# BiSheA.net
KiCad netlist of a schematic drawn in Altium Designer
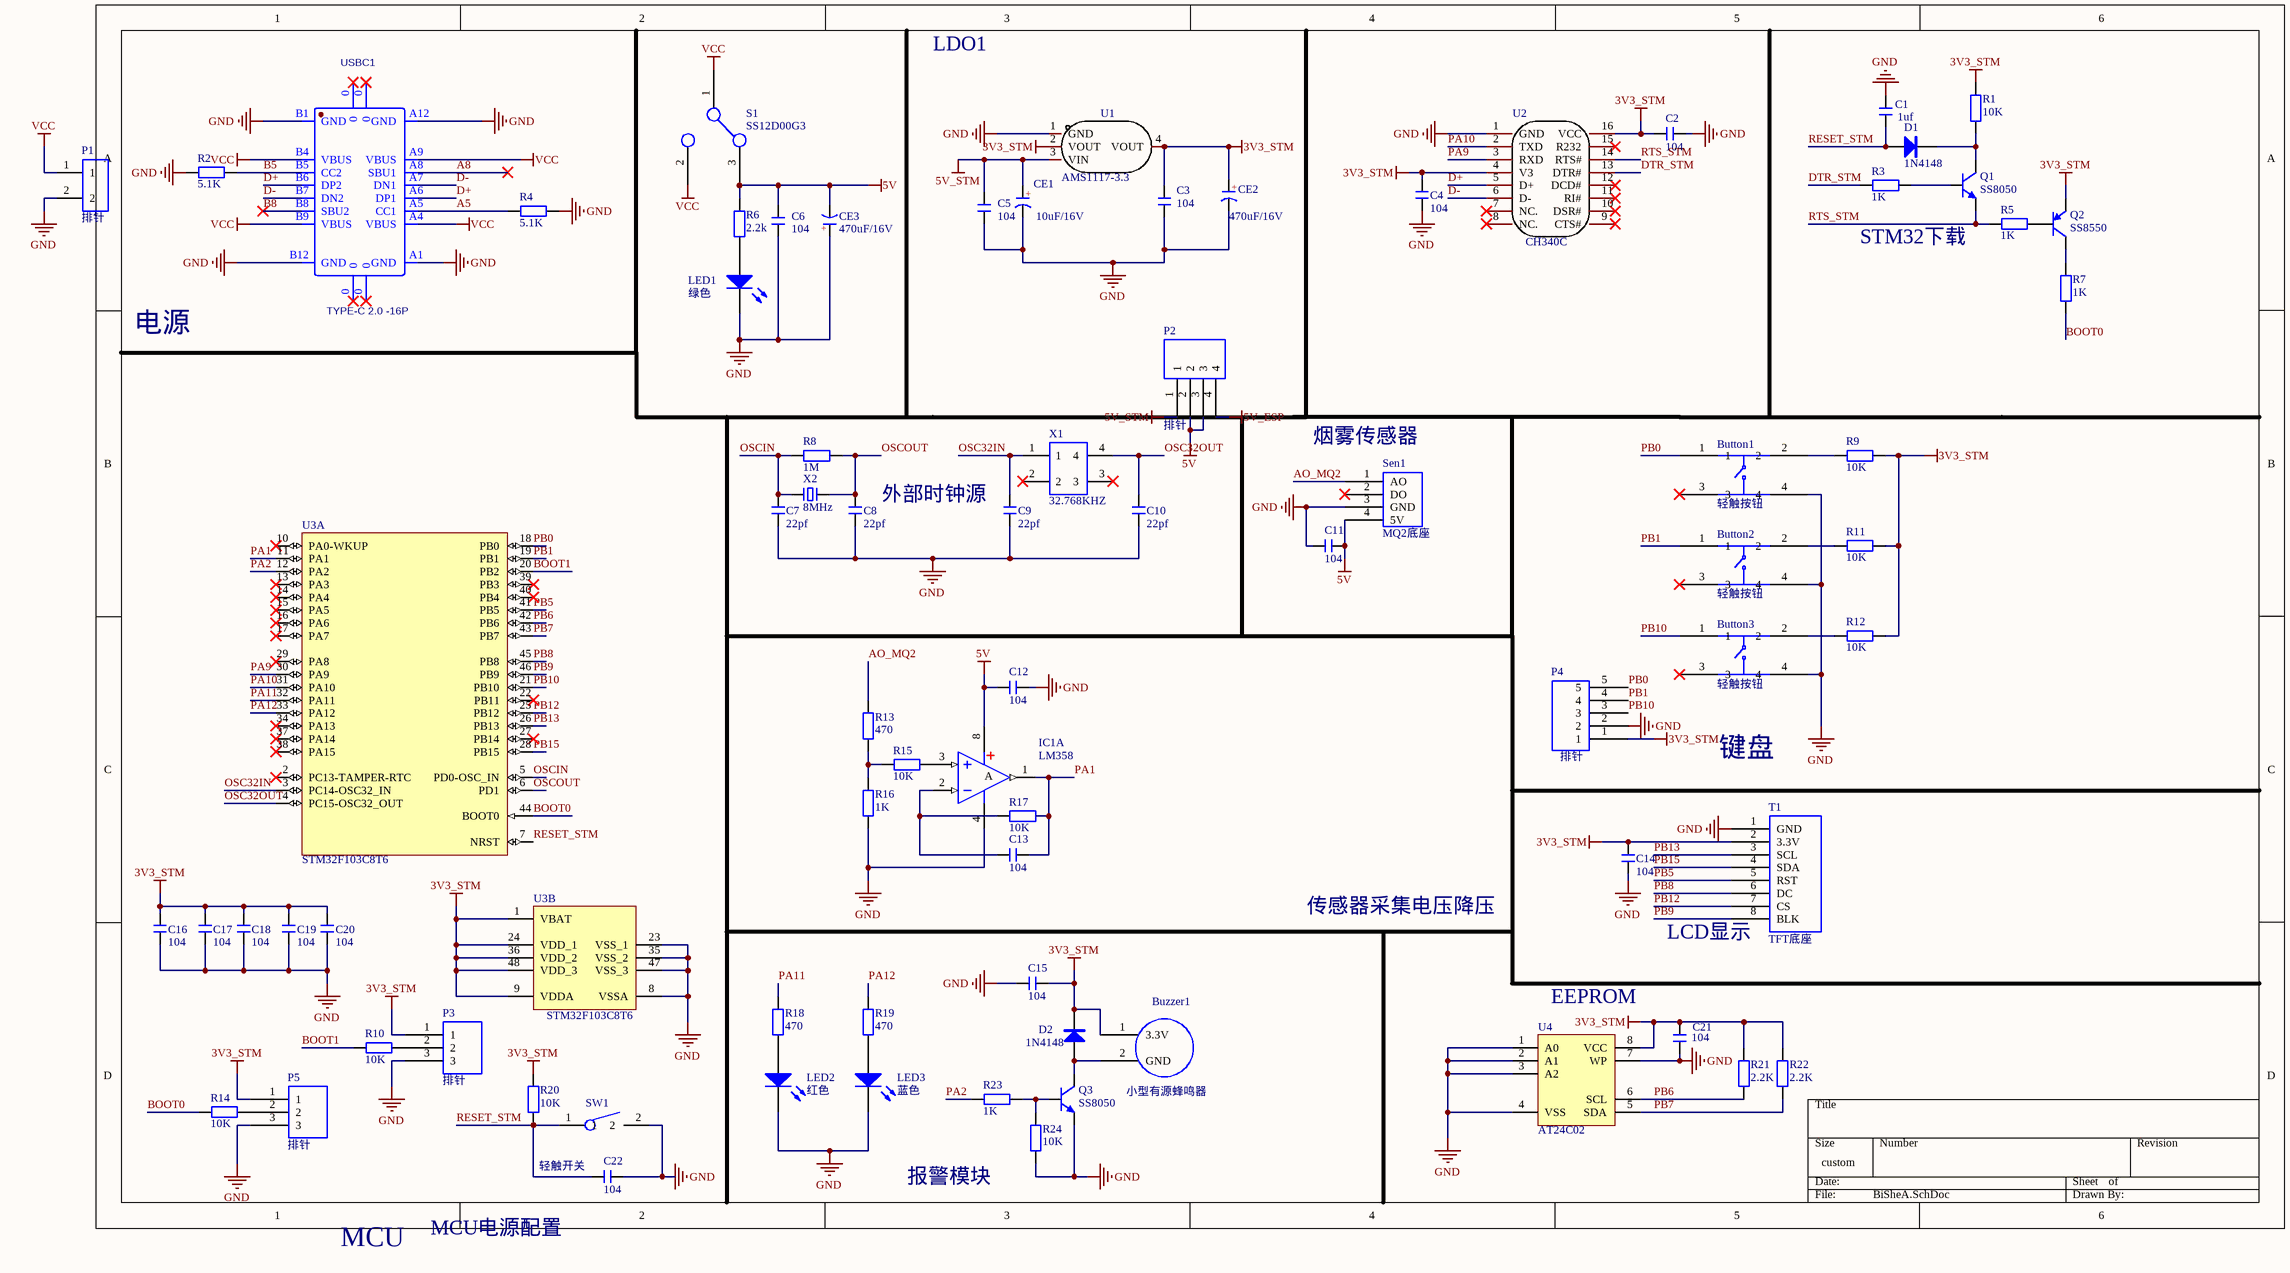
[diagram p0: BiSheA.SchDoc]

(export (version "E")
  (design (tool "Eeschema 10.0.6"))
  (components
    (comp (ref "Button1")
      (value "轻触按钮")
      (footprint "Button")
      (description "6*6*7轻触按钮")
      (libsource (lib "BiShe") (part "Button"))
    )
    (comp (ref "Button2")
      (value "轻触按钮")
      (footprint "Button")
      (description "6*6*7轻触按钮")
      (libsource (lib "BiShe") (part "Button"))
    )
    (comp (ref "Button3")
      (value "轻触按钮")
      (footprint "Button")
      (description "6*6*7轻触按钮")
      (libsource (lib "BiShe") (part "Button"))
    )
    (comp (ref "Buzzer1")
      (value "小型有源蜂鸣器")
      (footprint "Buzzer_Mini")
      (description "蜂鸣器")
      (libsource (lib "BiSheFinal") (part "Buzzer"))
    )
    (comp (ref "C1")
      (value "1uf")
      (footprint "C 0805_L")
      (description "贴片电容")
      (libsource (lib "0.1 - 电阻-电容-电感") (part "C"))
    )
    (comp (ref "C2")
      (value "104")
      (footprint "C 0805_L")
      (description "贴片电容")
      (libsource (lib "0.1 - 电阻-电容-电感") (part "C"))
    )
    (comp (ref "C3")
      (value "104")
      (footprint "C 0805_L")
      (description "贴片电容")
      (libsource (lib "0.1 - 电阻-电容-电感") (part "C"))
    )
    (comp (ref "C4")
      (value "104")
      (footprint "C 0805_L")
      (description "贴片电容")
      (libsource (lib "0.1 - 电阻-电容-电感") (part "C"))
    )
    (comp (ref "C5")
      (value "104")
      (footprint "C 0805_L")
      (description "贴片电容")
      (libsource (lib "0.1 - 电阻-电容-电感") (part "C"))
    )
    (comp (ref "C6")
      (value "104")
      (footprint "C 0805_L")
      (description "贴片电容")
      (libsource (lib "0.1 - 电阻-电容-电感") (part "C"))
    )
    (comp (ref "C7")
      (value "22pf")
      (footprint "C 0805_L")
      (description "贴片电容")
      (libsource (lib "0.1 - 电阻-电容-电感") (part "C"))
    )
    (comp (ref "C8")
      (value "22pf")
      (footprint "C 0805_L")
      (description "贴片电容")
      (libsource (lib "0.1 - 电阻-电容-电感") (part "C"))
    )
    (comp (ref "C9")
      (value "22pf")
      (footprint "C 0805_L")
      (description "贴片电容")
      (libsource (lib "0.1 - 电阻-电容-电感") (part "C"))
    )
    (comp (ref "C10")
      (value "22pf")
      (footprint "C 0805_L")
      (description "贴片电容")
      (libsource (lib "0.1 - 电阻-电容-电感") (part "C"))
    )
    (comp (ref "C11")
      (value "104")
      (footprint "C 0805_L")
      (description "贴片电容")
      (libsource (lib "0.1 - 电阻-电容-电感") (part "C"))
    )
    (comp (ref "C12")
      (value "104")
      (footprint "C 0805_L")
      (description "贴片电容")
      (libsource (lib "0.1 - 电阻-电容-电感") (part "C"))
    )
    (comp (ref "C13")
      (value "104")
      (footprint "C 0805_L")
      (description "贴片电容")
      (libsource (lib "0.1 - 电阻-电容-电感") (part "C"))
    )
    (comp (ref "C14")
      (value "104")
      (footprint "C 0805_L")
      (description "贴片电容")
      (libsource (lib "0.1 - 电阻-电容-电感") (part "C"))
    )
    (comp (ref "C15")
      (value "104")
      (footprint "C 0805_L")
      (description "贴片电容")
      (libsource (lib "0.1 - 电阻-电容-电感") (part "C"))
    )
    (comp (ref "C16")
      (value "104")
      (footprint "C 0805_L")
      (description "贴片电容")
      (libsource (lib "0.1 - 电阻-电容-电感") (part "C"))
    )
    (comp (ref "C17")
      (value "104")
      (footprint "C 0805_L")
      (description "贴片电容")
      (libsource (lib "0.1 - 电阻-电容-电感") (part "C"))
    )
    (comp (ref "C18")
      (value "104")
      (footprint "C 0805_L")
      (description "贴片电容")
      (libsource (lib "0.1 - 电阻-电容-电感") (part "C"))
    )
    (comp (ref "C19")
      (value "104")
      (footprint "C 0805_L")
      (description "贴片电容")
      (libsource (lib "0.1 - 电阻-电容-电感") (part "C"))
    )
    (comp (ref "C20")
      (value "104")
      (footprint "C 0805_L")
      (description "贴片电容")
      (libsource (lib "0.1 - 电阻-电容-电感") (part "C"))
    )
    (comp (ref "C21")
      (value "104")
      (footprint "C 0805_L")
      (description "贴片电容")
      (libsource (lib "0.1 - 电阻-电容-电感") (part "C"))
    )
    (comp (ref "C22")
      (value "104")
      (footprint "C 0805_L")
      (description "贴片电容")
      (libsource (lib "0.1 - 电阻-电容-电感") (part "C"))
    )
    (comp (ref "CE1")
      (value "10uF/16V")
      (footprint "CAP 1.5*4*8")
      (description "直插电解电容")
      (libsource (lib "0.1 - 电阻-电容-电感") (part "CE"))
    )
    (comp (ref "CE2")
      (value "470uF/16V")
      (footprint "CAP 3.5*8*11.5")
      (description "直插电解电容")
      (libsource (lib "0.1 - 电阻-电容-电感") (part "CE"))
    )
    (comp (ref "CE3")
      (value "470uF/16V")
      (footprint "CAP 3.5*8*11.5")
      (description "直插电解电容")
      (libsource (lib "0.1 - 电阻-电容-电感") (part "CE"))
    )
    (comp (ref "D1")
      (value "1N4148")
      (footprint "SOD-123")
      (description "开关二极管")
      (libsource (lib "0.2 - 二极管-整流桥") (part "1N4148"))
    )
    (comp (ref "D2")
      (value "1N4148")
      (footprint "SOD-123")
      (description "开关二极管")
      (libsource (lib "0.2 - 二极管-整流桥") (part "1N4148"))
    )
    (comp (ref "IC1")
      (value "LM358")
      (footprint "SOP8_N")
      (description "双路运放")
      (libsource (lib "1.0 - 常见芯片") (part "LM358"))
    )
    (comp (ref "LED1")
      (value "绿色")
      (footprint "LED 5MM-B")
      (description "直插5mm LED")
      (fields (field (name "版权归属") "封装库来自淘宝 ID：黄晶宝石"))
      (libsource (lib "0.3 - LED发光二极管") (part "LED-5MM"))
    )
    (comp (ref "LED2")
      (value "红色")
      (footprint "LED 5MM-B")
      (description "直插5mm LED")
      (fields (field (name "版权归属") "封装库来自淘宝 ID：黄晶宝石"))
      (libsource (lib "0.3 - LED发光二极管") (part "LED-5MM"))
    )
    (comp (ref "LED3")
      (value "蓝色")
      (footprint "LED 5MM-B")
      (description "直插5mm LED")
      (fields (field (name "版权归属") "封装库来自淘宝 ID：黄晶宝石"))
      (libsource (lib "0.3 - LED发光二极管") (part "LED-5MM"))
    )
    (comp (ref "P1")
      (value "排针")
      (footprint "2PIN")
      (description "2Pin排针")
      (libsource (lib "BiSheFinal") (part "2Pin"))
    )
    (comp (ref "P2")
      (value "排针")
      (footprint "4PIN")
      (description "4p排针")
      (libsource (lib "BiSheFinal") (part "4Pin"))
    )
    (comp (ref "P3")
      (value "排针")
      (footprint "3Pin")
      (description "3p排针")
      (libsource (lib "BiSheFinal") (part "3Pin"))
    )
    (comp (ref "P4")
      (value "排针")
      (footprint "5pin")
      (description "5Pin排针")
      (libsource (lib "BiSheFinal") (part "5Pin"))
    )
    (comp (ref "P5")
      (value "排针")
      (footprint "3Pin")
      (description "3p排针")
      (libsource (lib "BiSheFinal") (part "3Pin"))
    )
    (comp (ref "Q1")
      (value "SS8050")
      (footprint "SOT23-3N")
      (description "高频放大-NPN型")
      (fields (field (name "版权归属") "封装库来自淘宝 ID：黄晶宝石"))
      (libsource (lib "0.4 - 三极管") (part "8050-SMD"))
    )
    (comp (ref "Q2")
      (value "SS8550")
      (footprint "SOT23-3N")
      (description "高频放大-PNP型")
      (fields (field (name "版权归属") "封装库来自淘宝 ID：黄晶宝石"))
      (libsource (lib "0.4 - 三极管") (part "8550-SMD"))
    )
    (comp (ref "Q3")
      (value "SS8050")
      (footprint "SOT23-3N")
      (description "高频放大-NPN型")
      (fields (field (name "版权归属") "封装库来自淘宝 ID：黄晶宝石"))
      (libsource (lib "0.4 - 三极管") (part "8050-SMD"))
    )
    (comp (ref "R1")
      (value "10K")
      (footprint "R 0805_L")
      (description "贴片电阻")
      (fields (field (name "版权归属") "来自淘宝 ID：黄晶宝石"))
      (libsource (lib "0.1 - 电阻-电容-电感") (part "R"))
    )
    (comp (ref "R2")
      (value "5.1K")
      (footprint "R 0805_L")
      (description "贴片电阻")
      (fields (field (name "版权归属") "来自淘宝 ID：黄晶宝石"))
      (libsource (lib "0.1 - 电阻-电容-电感") (part "R"))
    )
    (comp (ref "R3")
      (value "1K")
      (footprint "R 0805_L")
      (description "贴片电阻")
      (fields (field (name "版权归属") "来自淘宝 ID：黄晶宝石"))
      (libsource (lib "0.1 - 电阻-电容-电感") (part "R"))
    )
    (comp (ref "R4")
      (value "5.1K")
      (footprint "R 0805_L")
      (description "贴片电阻")
      (fields (field (name "版权归属") "来自淘宝 ID：黄晶宝石"))
      (libsource (lib "0.1 - 电阻-电容-电感") (part "R"))
    )
    (comp (ref "R5")
      (value "1K")
      (footprint "R 0805_L")
      (description "贴片电阻")
      (fields (field (name "版权归属") "来自淘宝 ID：黄晶宝石"))
      (libsource (lib "0.1 - 电阻-电容-电感") (part "R"))
    )
    (comp (ref "R6")
      (value "2.2k")
      (footprint "R 0805_L")
      (description "贴片电阻")
      (fields (field (name "版权归属") "来自淘宝 ID：黄晶宝石"))
      (libsource (lib "0.1 - 电阻-电容-电感") (part "R"))
    )
    (comp (ref "R7")
      (value "1K")
      (footprint "R 0805_L")
      (description "贴片电阻")
      (fields (field (name "版权归属") "来自淘宝 ID：黄晶宝石"))
      (libsource (lib "0.1 - 电阻-电容-电感") (part "R"))
    )
    (comp (ref "R8")
      (value "1M")
      (footprint "R 0805_L")
      (description "贴片电阻")
      (fields (field (name "版权归属") "来自淘宝 ID：黄晶宝石"))
      (libsource (lib "0.1 - 电阻-电容-电感") (part "R"))
    )
    (comp (ref "R9")
      (value "10K")
      (footprint "R 0805_L")
      (description "贴片电阻")
      (fields (field (name "版权归属") "来自淘宝 ID：黄晶宝石"))
      (libsource (lib "0.1 - 电阻-电容-电感") (part "R"))
    )
    (comp (ref "R10")
      (value "10K")
      (footprint "R 0805_L")
      (description "贴片电阻")
      (fields (field (name "版权归属") "来自淘宝 ID：黄晶宝石"))
      (libsource (lib "0.1 - 电阻-电容-电感") (part "R"))
    )
    (comp (ref "R11")
      (value "10K")
      (footprint "R 0805_L")
      (description "贴片电阻")
      (fields (field (name "版权归属") "来自淘宝 ID：黄晶宝石"))
      (libsource (lib "0.1 - 电阻-电容-电感") (part "R"))
    )
    (comp (ref "R12")
      (value "10K")
      (footprint "R 0805_L")
      (description "贴片电阻")
      (fields (field (name "版权归属") "来自淘宝 ID：黄晶宝石"))
      (libsource (lib "0.1 - 电阻-电容-电感") (part "R"))
    )
    (comp (ref "R13")
      (value "470")
      (footprint "R 0805_L")
      (description "贴片电阻")
      (fields (field (name "版权归属") "来自淘宝 ID：黄晶宝石"))
      (libsource (lib "0.1 - 电阻-电容-电感") (part "R"))
    )
    (comp (ref "R14")
      (value "10K")
      (footprint "R 0805_L")
      (description "贴片电阻")
      (fields (field (name "版权归属") "来自淘宝 ID：黄晶宝石"))
      (libsource (lib "0.1 - 电阻-电容-电感") (part "R"))
    )
    (comp (ref "R15")
      (value "10K")
      (footprint "R 0805_L")
      (description "贴片电阻")
      (fields (field (name "版权归属") "来自淘宝 ID：黄晶宝石"))
      (libsource (lib "0.1 - 电阻-电容-电感") (part "R"))
    )
    (comp (ref "R16")
      (value "1K")
      (footprint "R 0805_L")
      (description "贴片电阻")
      (fields (field (name "版权归属") "来自淘宝 ID：黄晶宝石"))
      (libsource (lib "0.1 - 电阻-电容-电感") (part "R"))
    )
    (comp (ref "R17")
      (value "10K")
      (footprint "R 0805_L")
      (description "贴片电阻")
      (fields (field (name "版权归属") "来自淘宝 ID：黄晶宝石"))
      (libsource (lib "0.1 - 电阻-电容-电感") (part "R"))
    )
    (comp (ref "R18")
      (value "470")
      (footprint "R 0805_L")
      (description "贴片电阻")
      (fields (field (name "版权归属") "来自淘宝 ID：黄晶宝石"))
      (libsource (lib "0.1 - 电阻-电容-电感") (part "R"))
    )
    (comp (ref "R19")
      (value "470")
      (footprint "R 0805_L")
      (description "贴片电阻")
      (fields (field (name "版权归属") "来自淘宝 ID：黄晶宝石"))
      (libsource (lib "0.1 - 电阻-电容-电感") (part "R"))
    )
    (comp (ref "R20")
      (value "10K")
      (footprint "R 0805_L")
      (description "贴片电阻")
      (fields (field (name "版权归属") "来自淘宝 ID：黄晶宝石"))
      (libsource (lib "0.1 - 电阻-电容-电感") (part "R"))
    )
    (comp (ref "R21")
      (value "2.2K")
      (footprint "R 0805_L")
      (description "贴片电阻")
      (fields (field (name "版权归属") "来自淘宝 ID：黄晶宝石"))
      (libsource (lib "0.1 - 电阻-电容-电感") (part "R"))
    )
    (comp (ref "R22")
      (value "2.2K")
      (footprint "R 0805_L")
      (description "贴片电阻")
      (fields (field (name "版权归属") "来自淘宝 ID：黄晶宝石"))
      (libsource (lib "0.1 - 电阻-电容-电感") (part "R"))
    )
    (comp (ref "R23")
      (value "1K")
      (footprint "R 0805_L")
      (description "贴片电阻")
      (fields (field (name "版权归属") "来自淘宝 ID：黄晶宝石"))
      (libsource (lib "0.1 - 电阻-电容-电感") (part "R"))
    )
    (comp (ref "R24")
      (value "10K")
      (footprint "R 0805_L")
      (description "贴片电阻")
      (fields (field (name "版权归属") "来自淘宝 ID：黄晶宝石"))
      (libsource (lib "0.1 - 电阻-电容-电感") (part "R"))
    )
    (comp (ref "S1")
      (value "SS12D00G3")
      (footprint "SS12D00G3")
      (description "拨动开关")
      (libsource (lib "BiSheFinal") (part "SS12D00G3"))
    )
    (comp (ref "Sen1")
      (value "MQ2底座")
      (footprint "MQ2底座")
      (description "气体传感器")
      (libsource (lib "BiSheFinal") (part "MQ2底座"))
    )
    (comp (ref "SW1")
      (value "轻触开关")
      (footprint "SW1P")
      (description "单刀单掷清除开关")
      (libsource (lib "BiSheFinal") (part "SW1P"))
    )
    (comp (ref "T1")
      (value "TFT底座")
      (footprint "TFT底座")
      (description "底座")
      (libsource (lib "BiSheFinal") (part "TFT底座"))
    )
    (comp (ref "U1")
      (value "AMS1117-3.3")
      (footprint "SOT-223-3_L6.5-W3.4-P2.30-LS7.0-BR")
      (description "输出类型:固定;输出极性:正;最大输入电压:-;输出电压:3.3V;输出电流:1A;电源纹波抑制比(PSRR):72dB@(120Hz);")
      (fields (field (name "MANUFACTURER") "AMS") (field (name "AMS1117") "AMS1117-3.3"))
      (libsource (lib "BiSheFinal") (part "AMS1117-3.3_C6186"))
    )
    (comp (ref "U2")
      (value "CH340C")
      (footprint "SOP-16_L10.0-W3.9-P1.27-LS6.0-BL")
      (description "驱动器/接收器数:-;协议类别:USB 2.0;类型:Transceiver;数据速率:2Mbps;")
      (fields (field (name "MANUFACTURER") "WCH(南京沁恒)") (field (name "CH340C") "CH340C"))
      (libsource (lib "BiSheFinal") (part "CH340C"))
    )
    (comp (ref "U3")
      (value "STM32F103C8T6")
      (footprint "LQFP48_N")
      (libsource (lib "2.3 - STM32 F1系列单片机") (part "STM32F103C8T6"))
    )
    (comp (ref "U4")
      (value "AT24C02")
      (footprint "SOIC8_N")
      (description "EEROM存储器")
      (libsource (lib "1.0 - 常见芯片") (part "AT24C02"))
    )
    (comp (ref "USBC1")
      (value "TYPE-C 2.0 -16P")
      (footprint "USB-C-SMD_TYPE-C-USB-5")
      (description "USB2.0 Type-C 母座 16Pin")
      (libsource (lib "BiSheFinal") (part "USB2.0 Type-C 16Pin母座"))
    )
    (comp (ref "X1")
      (value "32.768KHZ")
      (footprint "MC-306")
      (description "贴片32.768KHZ")
      (libsource (lib "BiSheFinal") (part "MC-306"))
    )
    (comp (ref "X2")
      (value "8MHz")
      (footprint "OSC HC-49S")
      (description "2脚无源脚晶振")
      (fields (field (name "版权归属") "封装库来自淘宝卖家 ID：黄晶宝石"))
      (libsource (lib "2.0 - 保险丝-晶振-光耦") (part "XTAL-2P"))
    )
  )
  (nets
    (net (code "1") (name "/A5") (class "Default")
      (node (ref "R4") (pin "2") (pinfunction "2_2") (pintype "passive"))
      (node (ref "USBC1") (pin "A5") (pinfunction "CC1_A5") (pintype "passive"))
    )
    (net (code "2") (name "/A8") (class "Default")
      (node (ref "USBC1") (pin "A8") (pinfunction "SBU1_A8") (pintype "passive+no_connect"))
    )
    (net (code "3") (name "/AO_MQ2") (class "Default")
      (node (ref "R13") (pin "1") (pinfunction "1_1") (pintype "passive"))
      (node (ref "Sen1") (pin "1") (pinfunction "AO_1") (pintype "passive"))
    )
    (net (code "4") (name "/B5") (class "Default")
      (node (ref "R2") (pin "1") (pinfunction "1_1") (pintype "passive"))
      (node (ref "USBC1") (pin "B5") (pinfunction "CC2_B5") (pintype "passive"))
    )
    (net (code "5") (name "/B8") (class "Default")
      (node (ref "USBC1") (pin "B8") (pinfunction "SBU2_B8") (pintype "passive+no_connect"))
    )
    (net (code "6") (name "/BOOT0") (class "Default")
      (node (ref "R14") (pin "2") (pinfunction "2_2") (pintype "passive"))
      (node (ref "R7") (pin "2") (pinfunction "2_2") (pintype "passive"))
      (node (ref "U3") (pin "44") (pinfunction "BOOT0_44") (pintype "input"))
    )
    (net (code "7") (name "/BOOT1") (class "Default")
      (node (ref "R10") (pin "2") (pinfunction "2_2") (pintype "passive"))
      (node (ref "U3") (pin "20") (pinfunction "PB2_20") (pintype "bidirectional"))
    )
    (net (code "8") (name "/D+") (class "Default")
      (node (ref "U2") (pin "5") (pinfunction "D+_5") (pintype "passive"))
      (node (ref "USBC1") (pin "A6") (pinfunction "DP1_A6") (pintype "passive"))
      (node (ref "USBC1") (pin "B6") (pinfunction "DP2_B6") (pintype "passive"))
    )
    (net (code "9") (name "/D-") (class "Default")
      (node (ref "U2") (pin "6") (pinfunction "D-_6") (pintype "passive"))
      (node (ref "USBC1") (pin "A7") (pinfunction "DN1_A7") (pintype "passive"))
      (node (ref "USBC1") (pin "B7") (pinfunction "DN2_B7") (pintype "passive"))
    )
    (net (code "10") (name "/DTR_STM") (class "Default")
      (node (ref "R3") (pin "1") (pinfunction "1_1") (pintype "passive"))
      (node (ref "U2") (pin "13") (pinfunction "DTR#_13") (pintype "passive"))
    )
    (net (code "11") (name "/OSC32IN") (class "Default")
      (node (ref "C9") (pin "1") (pinfunction "1_1") (pintype "passive"))
      (node (ref "U3") (pin "3") (pinfunction "PC14-OSC32_IN_3") (pintype "bidirectional"))
      (node (ref "X1") (pin "1") (pinfunction "1_1") (pintype "passive"))
    )
    (net (code "12") (name "/OSC32OUT") (class "Default")
      (node (ref "C10") (pin "1") (pinfunction "1_1") (pintype "passive"))
      (node (ref "U3") (pin "4") (pinfunction "PC15-OSC32_OUT_4") (pintype "bidirectional"))
      (node (ref "X1") (pin "4") (pinfunction "4_4") (pintype "passive"))
    )
    (net (code "13") (name "/OSCIN") (class "Default")
      (node (ref "C7") (pin "1") (pinfunction "1_1") (pintype "passive"))
      (node (ref "R8") (pin "2") (pinfunction "2_2") (pintype "passive"))
      (node (ref "U3") (pin "5") (pinfunction "PD0-OSC_IN_5") (pintype "bidirectional"))
      (node (ref "X2") (pin "1") (pinfunction "1_1") (pintype "passive"))
    )
    (net (code "14") (name "/OSCOUT") (class "Default")
      (node (ref "C8") (pin "1") (pinfunction "1_1") (pintype "passive"))
      (node (ref "R8") (pin "1") (pinfunction "1_1") (pintype "passive"))
      (node (ref "U3") (pin "6") (pinfunction "PD1_6") (pintype "bidirectional"))
      (node (ref "X2") (pin "2") (pinfunction "2_2") (pintype "passive"))
    )
    (net (code "15") (name "/PA1") (class "Default")
      (node (ref "C13") (pin "1") (pinfunction "1_1") (pintype "passive"))
      (node (ref "IC1") (pin "1") (pinfunction "OUT_1") (pintype "output"))
      (node (ref "R17") (pin "1") (pinfunction "1_1") (pintype "passive"))
      (node (ref "U3") (pin "11") (pinfunction "PA1_11") (pintype "bidirectional"))
    )
    (net (code "16") (name "/PA2") (class "Default")
      (node (ref "R23") (pin "1") (pinfunction "1_1") (pintype "passive"))
      (node (ref "U3") (pin "12") (pinfunction "PA2_12") (pintype "bidirectional"))
    )
    (net (code "17") (name "/PA9") (class "Default")
      (node (ref "U2") (pin "3") (pinfunction "RXD_3") (pintype "passive"))
      (node (ref "U3") (pin "30") (pinfunction "PA9_30") (pintype "bidirectional"))
    )
    (net (code "18") (name "/PA10") (class "Default")
      (node (ref "U2") (pin "2") (pinfunction "TXD_2") (pintype "passive"))
      (node (ref "U3") (pin "31") (pinfunction "PA10_31") (pintype "bidirectional"))
    )
    (net (code "19") (name "/PA11") (class "Default")
      (node (ref "R18") (pin "1") (pinfunction "1_1") (pintype "passive"))
      (node (ref "U3") (pin "32") (pinfunction "PA11_32") (pintype "bidirectional"))
    )
    (net (code "20") (name "/PA12") (class "Default")
      (node (ref "R19") (pin "1") (pinfunction "1_1") (pintype "passive"))
      (node (ref "U3") (pin "33") (pinfunction "PA12_33") (pintype "bidirectional"))
    )
    (net (code "21") (name "/PB0") (class "Default")
      (node (ref "Button1") (pin "1") (pinfunction "1_1") (pintype "passive"))
      (node (ref "P4") (pin "5") (pinfunction "5_5") (pintype "passive"))
      (node (ref "U3") (pin "18") (pinfunction "PB0_18") (pintype "bidirectional"))
    )
    (net (code "22") (name "/PB1") (class "Default")
      (node (ref "Button2") (pin "1") (pinfunction "1_1") (pintype "passive"))
      (node (ref "P4") (pin "4") (pinfunction "4_4") (pintype "passive"))
      (node (ref "U3") (pin "19") (pinfunction "PB1_19") (pintype "bidirectional"))
    )
    (net (code "23") (name "/PB5") (class "Default")
      (node (ref "T1") (pin "5") (pinfunction "RST_5") (pintype "passive"))
      (node (ref "U3") (pin "41") (pinfunction "PB5_41") (pintype "bidirectional"))
    )
    (net (code "24") (name "/PB6") (class "Default")
      (node (ref "R21") (pin "2") (pinfunction "2_2") (pintype "passive"))
      (node (ref "U3") (pin "42") (pinfunction "PB6_42") (pintype "bidirectional"))
      (node (ref "U4") (pin "6") (pinfunction "SCL_6") (pintype "passive"))
    )
    (net (code "25") (name "/PB7") (class "Default")
      (node (ref "R22") (pin "2") (pinfunction "2_2") (pintype "passive"))
      (node (ref "U3") (pin "43") (pinfunction "PB7_43") (pintype "bidirectional"))
      (node (ref "U4") (pin "5") (pinfunction "SDA_5") (pintype "passive"))
    )
    (net (code "26") (name "/PB8") (class "Default")
      (node (ref "T1") (pin "6") (pinfunction "DC_6") (pintype "passive"))
      (node (ref "U3") (pin "45") (pinfunction "PB8_45") (pintype "bidirectional"))
    )
    (net (code "27") (name "/PB9") (class "Default")
      (node (ref "T1") (pin "8") (pinfunction "BLK_8") (pintype "passive"))
      (node (ref "U3") (pin "46") (pinfunction "PB9_46") (pintype "bidirectional"))
    )
    (net (code "28") (name "/PB10") (class "Default")
      (node (ref "Button3") (pin "1") (pinfunction "1_1") (pintype "passive"))
      (node (ref "P4") (pin "3") (pinfunction "3_3") (pintype "passive"))
      (node (ref "U3") (pin "21") (pinfunction "PB10_21") (pintype "bidirectional"))
    )
    (net (code "29") (name "/PB12") (class "Default")
      (node (ref "T1") (pin "7") (pinfunction "CS_7") (pintype "passive"))
      (node (ref "U3") (pin "25") (pinfunction "PB12_25") (pintype "bidirectional"))
    )
    (net (code "30") (name "/PB13") (class "Default")
      (node (ref "T1") (pin "3") (pinfunction "SCL_3") (pintype "passive"))
      (node (ref "U3") (pin "26") (pinfunction "PB13_26") (pintype "bidirectional"))
    )
    (net (code "31") (name "/PB15") (class "Default")
      (node (ref "T1") (pin "4") (pinfunction "SDA_4") (pintype "passive"))
      (node (ref "U3") (pin "28") (pinfunction "PB15_28") (pintype "bidirectional"))
    )
    (net (code "32") (name "/RESET_STM") (class "Default")
      (node (ref "C1") (pin "2") (pinfunction "2_2") (pintype "passive"))
      (node (ref "C22") (pin "1") (pinfunction "1_1") (pintype "passive"))
      (node (ref "D1") (pin "1") (pinfunction "A_1") (pintype "passive"))
      (node (ref "R20") (pin "2") (pinfunction "2_2") (pintype "passive"))
      (node (ref "SW1") (pin "1") (pinfunction "1_1") (pintype "passive"))
      (node (ref "U3") (pin "7") (pinfunction "NRST_7") (pintype "bidirectional"))
    )
    (net (code "33") (name "/RTS_STM") (class "Default")
      (node (ref "Q1") (pin "2") (pinfunction "E_2") (pintype "passive"))
      (node (ref "R5") (pin "1") (pinfunction "1_1") (pintype "passive"))
      (node (ref "U2") (pin "14") (pinfunction "RTS#_14") (pintype "passive"))
    )
    (net (code "34") (name "3V3_STM") (class "Default")
      (node (ref "Buzzer1") (pin "1") (pinfunction "3.3V_1") (pintype "passive"))
      (node (ref "C14") (pin "2") (pinfunction "2_2") (pintype "passive"))
      (node (ref "C15") (pin "2") (pinfunction "2_2") (pintype "passive"))
      (node (ref "C16") (pin "1") (pinfunction "1_1") (pintype "passive"))
      (node (ref "C17") (pin "1") (pinfunction "1_1") (pintype "passive"))
      (node (ref "C18") (pin "1") (pinfunction "1_1") (pintype "passive"))
      (node (ref "C19") (pin "1") (pinfunction "1_1") (pintype "passive"))
      (node (ref "C2") (pin "1") (pinfunction "1_1") (pintype "passive"))
      (node (ref "C20") (pin "1") (pinfunction "1_1") (pintype "passive"))
      (node (ref "C21") (pin "2") (pinfunction "2_2") (pintype "passive"))
      (node (ref "C3") (pin "2") (pinfunction "2_2") (pintype "passive"))
      (node (ref "C4") (pin "2") (pinfunction "2_2") (pintype "passive"))
      (node (ref "CE2") (pin "1") (pinfunction "A_1") (pintype "passive"))
      (node (ref "D2") (pin "2") (pinfunction "K_2") (pintype "passive"))
      (node (ref "P3") (pin "1") (pinfunction "1_1") (pintype "passive"))
      (node (ref "P4") (pin "1") (pinfunction "1_1") (pintype "passive"))
      (node (ref "P5") (pin "1") (pinfunction "1_1") (pintype "passive"))
      (node (ref "Q2") (pin "2") (pinfunction "E_2") (pintype "passive"))
      (node (ref "R1") (pin "1") (pinfunction "1_1") (pintype "passive"))
      (node (ref "R11") (pin "1") (pinfunction "1_1") (pintype "passive"))
      (node (ref "R12") (pin "1") (pinfunction "1_1") (pintype "passive"))
      (node (ref "R20") (pin "1") (pinfunction "1_1") (pintype "passive"))
      (node (ref "R21") (pin "1") (pinfunction "1_1") (pintype "passive"))
      (node (ref "R22") (pin "1") (pinfunction "1_1") (pintype "passive"))
      (node (ref "R9") (pin "1") (pinfunction "1_1") (pintype "passive"))
      (node (ref "T1") (pin "2") (pinfunction "3.3V_2") (pintype "passive"))
      (node (ref "U1") (pin "2") (pinfunction "VOUT_2") (pintype "passive"))
      (node (ref "U1") (pin "4") (pinfunction "VOUT_4") (pintype "passive"))
      (node (ref "U2") (pin "16") (pinfunction "VCC_16") (pintype "passive"))
      (node (ref "U2") (pin "4") (pinfunction "V3_4") (pintype "passive"))
      (node (ref "U3") (pin "1") (pinfunction "VBAT_1") (pintype "power_in"))
      (node (ref "U3") (pin "24") (pinfunction "VDD_1_24") (pintype "power_in"))
      (node (ref "U3") (pin "36") (pinfunction "VDD_2_36") (pintype "power_in"))
      (node (ref "U3") (pin "48") (pinfunction "VDD_3_48") (pintype "power_in"))
      (node (ref "U3") (pin "9") (pinfunction "VDDA_9") (pintype "power_in"))
      (node (ref "U4") (pin "8") (pinfunction "VCC_8") (pintype "passive"))
    )
    (net (code "35") (name "5V") (class "Default")
      (node (ref "C11") (pin "2") (pinfunction "2_2") (pintype "passive"))
      (node (ref "C12") (pin "2") (pinfunction "2_2") (pintype "passive"))
      (node (ref "C6") (pin "2") (pinfunction "2_2") (pintype "passive"))
      (node (ref "CE3") (pin "2") (pinfunction "K_2") (pintype "passive"))
      (node (ref "IC1") (pin "8") (pinfunction "V+_8") (pintype "power_in"))
      (node (ref "P2") (pin "2") (pinfunction "2_2") (pintype "passive"))
      (node (ref "P2") (pin "3") (pinfunction "3_3") (pintype "passive"))
      (node (ref "R6") (pin "1") (pinfunction "1_1") (pintype "passive"))
      (node (ref "S1") (pin "3") (pinfunction "3_3") (pintype "passive"))
      (node (ref "Sen1") (pin "4") (pinfunction "5V_4") (pintype "passive"))
    )
    (net (code "36") (name "5V_ESP") (class "Default")
      (node (ref "P2") (pin "4") (pinfunction "4_4") (pintype "passive"))
    )
    (net (code "37") (name "5V_STM") (class "Default")
      (node (ref "C5") (pin "2") (pinfunction "2_2") (pintype "passive"))
      (node (ref "CE1") (pin "1") (pinfunction "A_1") (pintype "passive"))
      (node (ref "P2") (pin "1") (pinfunction "1_1") (pintype "passive"))
      (node (ref "U1") (pin "3") (pinfunction "VIN_3") (pintype "passive"))
    )
    (net (code "38") (name "GND") (class "Default")
      (node (ref "Button1") (pin "4") (pinfunction "4_4") (pintype "passive"))
      (node (ref "Button2") (pin "4") (pinfunction "4_4") (pintype "passive"))
      (node (ref "Button3") (pin "4") (pinfunction "4_4") (pintype "passive"))
      (node (ref "C1") (pin "1") (pinfunction "1_1") (pintype "passive"))
      (node (ref "C10") (pin "2") (pinfunction "2_2") (pintype "passive"))
      (node (ref "C11") (pin "1") (pinfunction "1_1") (pintype "passive"))
      (node (ref "C12") (pin "1") (pinfunction "1_1") (pintype "passive"))
      (node (ref "C14") (pin "1") (pinfunction "1_1") (pintype "passive"))
      (node (ref "C15") (pin "1") (pinfunction "1_1") (pintype "passive"))
      (node (ref "C16") (pin "2") (pinfunction "2_2") (pintype "passive"))
      (node (ref "C17") (pin "2") (pinfunction "2_2") (pintype "passive"))
      (node (ref "C18") (pin "2") (pinfunction "2_2") (pintype "passive"))
      (node (ref "C19") (pin "2") (pinfunction "2_2") (pintype "passive"))
      (node (ref "C2") (pin "2") (pinfunction "2_2") (pintype "passive"))
      (node (ref "C20") (pin "2") (pinfunction "2_2") (pintype "passive"))
      (node (ref "C21") (pin "1") (pinfunction "1_1") (pintype "passive"))
      (node (ref "C22") (pin "2") (pinfunction "2_2") (pintype "passive"))
      (node (ref "C3") (pin "1") (pinfunction "1_1") (pintype "passive"))
      (node (ref "C4") (pin "1") (pinfunction "1_1") (pintype "passive"))
      (node (ref "C5") (pin "1") (pinfunction "1_1") (pintype "passive"))
      (node (ref "C6") (pin "1") (pinfunction "1_1") (pintype "passive"))
      (node (ref "C7") (pin "2") (pinfunction "2_2") (pintype "passive"))
      (node (ref "C8") (pin "2") (pinfunction "2_2") (pintype "passive"))
      (node (ref "C9") (pin "2") (pinfunction "2_2") (pintype "passive"))
      (node (ref "CE1") (pin "2") (pinfunction "K_2") (pintype "passive"))
      (node (ref "CE2") (pin "2") (pinfunction "K_2") (pintype "passive"))
      (node (ref "CE3") (pin "1") (pinfunction "A_1") (pintype "passive"))
      (node (ref "IC1") (pin "4") (pinfunction "V-_4") (pintype "power_in"))
      (node (ref "LED1") (pin "2") (pinfunction "K_2") (pintype "passive"))
      (node (ref "LED2") (pin "2") (pinfunction "K_2") (pintype "passive"))
      (node (ref "LED3") (pin "2") (pinfunction "K_2") (pintype "passive"))
      (node (ref "P1") (pin "2") (pinfunction "2_2") (pintype "passive"))
      (node (ref "P3") (pin "3") (pinfunction "3_3") (pintype "passive"))
      (node (ref "P4") (pin "2") (pinfunction "2_2") (pintype "passive"))
      (node (ref "P5") (pin "3") (pinfunction "3_3") (pintype "passive"))
      (node (ref "Q3") (pin "2") (pinfunction "E_2") (pintype "passive"))
      (node (ref "R16") (pin "2") (pinfunction "2_2") (pintype "passive"))
      (node (ref "R2") (pin "2") (pinfunction "2_2") (pintype "passive"))
      (node (ref "R24") (pin "2") (pinfunction "2_2") (pintype "passive"))
      (node (ref "R4") (pin "1") (pinfunction "1_1") (pintype "passive"))
      (node (ref "SW1") (pin "2") (pinfunction "2_2") (pintype "passive"))
      (node (ref "Sen1") (pin "3") (pinfunction "GND_3") (pintype "passive"))
      (node (ref "T1") (pin "1") (pinfunction "GND_1") (pintype "passive"))
      (node (ref "U1") (pin "1") (pinfunction "GND_1") (pintype "passive"))
      (node (ref "U2") (pin "1") (pinfunction "GND_1") (pintype "passive"))
      (node (ref "U3") (pin "23") (pinfunction "VSS_1_23") (pintype "power_in"))
      (node (ref "U3") (pin "35") (pinfunction "VSS_2_35") (pintype "power_in"))
      (node (ref "U3") (pin "47") (pinfunction "VSS_3_47") (pintype "power_in"))
      (node (ref "U3") (pin "8") (pinfunction "VSSA_8") (pintype "power_in"))
      (node (ref "U4") (pin "1") (pinfunction "A0_1") (pintype "passive"))
      (node (ref "U4") (pin "2") (pinfunction "A1_2") (pintype "passive"))
      (node (ref "U4") (pin "3") (pinfunction "A2_3") (pintype "passive"))
      (node (ref "U4") (pin "4") (pinfunction "VSS_4") (pintype "passive"))
      (node (ref "U4") (pin "7") (pinfunction "WP_7") (pintype "passive"))
      (node (ref "USBC1") (pin "A1") (pinfunction "GND_A1") (pintype "passive"))
      (node (ref "USBC1") (pin "A12") (pinfunction "GND_A12") (pintype "passive"))
      (node (ref "USBC1") (pin "B1") (pinfunction "GND_B1") (pintype "passive"))
      (node (ref "USBC1") (pin "B12") (pinfunction "GND_B12") (pintype "passive"))
    )
    (net (code "39") (name "Net-(Button1-Pad2)") (class "Default")
      (node (ref "Button1") (pin "2") (pinfunction "2_2") (pintype "passive"))
      (node (ref "R9") (pin "2") (pinfunction "2_2") (pintype "passive"))
    )
    (net (code "40") (name "Net-(Button2-Pad2)") (class "Default")
      (node (ref "Button2") (pin "2") (pinfunction "2_2") (pintype "passive"))
      (node (ref "R11") (pin "2") (pinfunction "2_2") (pintype "passive"))
    )
    (net (code "41") (name "Net-(Button3-Pad2)") (class "Default")
      (node (ref "Button3") (pin "2") (pinfunction "2_2") (pintype "passive"))
      (node (ref "R12") (pin "2") (pinfunction "2_2") (pintype "passive"))
    )
    (net (code "42") (name "Net-(Buzzer1-GND)") (class "Default")
      (node (ref "Buzzer1") (pin "2") (pinfunction "GND_2") (pintype "passive"))
      (node (ref "D2") (pin "1") (pinfunction "A_1") (pintype "passive"))
      (node (ref "Q3") (pin "3") (pinfunction "C_3") (pintype "passive"))
    )
    (net (code "43") (name "Net-(D1-K)") (class "Default")
      (node (ref "D1") (pin "2") (pinfunction "K_2") (pintype "passive"))
      (node (ref "Q1") (pin "3") (pinfunction "C_3") (pintype "passive"))
      (node (ref "R1") (pin "2") (pinfunction "2_2") (pintype "passive"))
    )
    (net (code "44") (name "Net-(IC1A-IN+)") (class "Default")
      (node (ref "IC1") (pin "3") (pinfunction "IN+_3") (pintype "input"))
      (node (ref "R15") (pin "1") (pinfunction "1_1") (pintype "passive"))
    )
    (net (code "45") (name "Net-(IC1A-IN-)") (class "Default")
      (node (ref "C13") (pin "2") (pinfunction "2_2") (pintype "passive"))
      (node (ref "IC1") (pin "2") (pinfunction "IN-_2") (pintype "input"))
      (node (ref "R17") (pin "2") (pinfunction "2_2") (pintype "passive"))
    )
    (net (code "46") (name "Net-(LED1-A)") (class "Default")
      (node (ref "LED1") (pin "1") (pinfunction "A_1") (pintype "passive"))
      (node (ref "R6") (pin "2") (pinfunction "2_2") (pintype "passive"))
    )
    (net (code "47") (name "Net-(LED2-A)") (class "Default")
      (node (ref "LED2") (pin "1") (pinfunction "A_1") (pintype "passive"))
      (node (ref "R18") (pin "2") (pinfunction "2_2") (pintype "passive"))
    )
    (net (code "48") (name "Net-(LED3-A)") (class "Default")
      (node (ref "LED3") (pin "1") (pinfunction "A_1") (pintype "passive"))
      (node (ref "R19") (pin "2") (pinfunction "2_2") (pintype "passive"))
    )
    (net (code "49") (name "Net-(P3-Pad2)") (class "Default")
      (node (ref "P3") (pin "2") (pinfunction "2_2") (pintype "passive"))
      (node (ref "R10") (pin "1") (pinfunction "1_1") (pintype "passive"))
    )
    (net (code "50") (name "Net-(P5-Pad2)") (class "Default")
      (node (ref "P5") (pin "2") (pinfunction "2_2") (pintype "passive"))
      (node (ref "R14") (pin "1") (pinfunction "1_1") (pintype "passive"))
    )
    (net (code "51") (name "Net-(Q1-B)") (class "Default")
      (node (ref "Q1") (pin "1") (pinfunction "B_1") (pintype "passive"))
      (node (ref "R3") (pin "2") (pinfunction "2_2") (pintype "passive"))
    )
    (net (code "52") (name "Net-(Q2-B)") (class "Default")
      (node (ref "Q2") (pin "1") (pinfunction "B_1") (pintype "passive"))
      (node (ref "R5") (pin "2") (pinfunction "2_2") (pintype "passive"))
    )
    (net (code "53") (name "Net-(Q2-C)") (class "Default")
      (node (ref "Q2") (pin "3") (pinfunction "C_3") (pintype "passive"))
      (node (ref "R7") (pin "1") (pinfunction "1_1") (pintype "passive"))
    )
    (net (code "54") (name "Net-(Q3-B)") (class "Default")
      (node (ref "Q3") (pin "1") (pinfunction "B_1") (pintype "passive"))
      (node (ref "R23") (pin "2") (pinfunction "2_2") (pintype "passive"))
      (node (ref "R24") (pin "1") (pinfunction "1_1") (pintype "passive"))
    )
    (net (code "55") (name "Net-(R13-Pad2)") (class "Default")
      (node (ref "R13") (pin "2") (pinfunction "2_2") (pintype "passive"))
      (node (ref "R15") (pin "2") (pinfunction "2_2") (pintype "passive"))
      (node (ref "R16") (pin "1") (pinfunction "1_1") (pintype "passive"))
    )
    (net (code "56") (name "VCC") (class "Default")
      (node (ref "P1") (pin "1") (pinfunction "1_1") (pintype "passive"))
      (node (ref "S1") (pin "1") (pinfunction "1_1") (pintype "passive"))
      (node (ref "S1") (pin "2") (pinfunction "2_2") (pintype "passive"))
      (node (ref "USBC1") (pin "A4") (pinfunction "VBUS_A4") (pintype "passive"))
      (node (ref "USBC1") (pin "A9") (pinfunction "VBUS_A9") (pintype "passive"))
      (node (ref "USBC1") (pin "B4") (pinfunction "VBUS_B4") (pintype "passive"))
      (node (ref "USBC1") (pin "B9") (pinfunction "VBUS_B9") (pintype "passive"))
    )
    (net (code "57") (name "unconnected-(Button1-Pad3)") (class "Default")
      (node (ref "Button1") (pin "3") (pinfunction "3_3") (pintype "passive+no_connect"))
    )
    (net (code "58") (name "unconnected-(Button2-Pad3)") (class "Default")
      (node (ref "Button2") (pin "3") (pinfunction "3_3") (pintype "passive+no_connect"))
    )
    (net (code "59") (name "unconnected-(Button3-Pad3)") (class "Default")
      (node (ref "Button3") (pin "3") (pinfunction "3_3") (pintype "passive+no_connect"))
    )
    (net (code "60") (name "unconnected-(Sen1-DO-Pad2)") (class "Default")
      (node (ref "Sen1") (pin "2") (pinfunction "DO_2") (pintype "passive+no_connect"))
    )
    (net (code "61") (name "unconnected-(U2-CTS#-Pad9)") (class "Default")
      (node (ref "U2") (pin "9") (pinfunction "CTS#_9") (pintype "passive+no_connect"))
    )
    (net (code "62") (name "unconnected-(U2-DCD#-Pad12)") (class "Default")
      (node (ref "U2") (pin "12") (pinfunction "DCD#_12") (pintype "passive+no_connect"))
    )
    (net (code "63") (name "unconnected-(U2-DSR#-Pad10)") (class "Default")
      (node (ref "U2") (pin "10") (pinfunction "DSR#_10") (pintype "passive+no_connect"))
    )
    (net (code "64") (name "unconnected-(U2-NC.-Pad7)") (class "Default")
      (node (ref "U2") (pin "7") (pinfunction "NC._7") (pintype "passive+no_connect"))
    )
    (net (code "65") (name "unconnected-(U2-NC.-Pad8)") (class "Default")
      (node (ref "U2") (pin "8") (pinfunction "NC._8") (pintype "passive+no_connect"))
    )
    (net (code "66") (name "unconnected-(U2-R232-Pad15)") (class "Default")
      (node (ref "U2") (pin "15") (pinfunction "R232_15") (pintype "passive+no_connect"))
    )
    (net (code "67") (name "unconnected-(U2-RI#-Pad11)") (class "Default")
      (node (ref "U2") (pin "11") (pinfunction "RI#_11") (pintype "passive+no_connect"))
    )
    (net (code "68") (name "unconnected-(U3A-PA0-WKUP-Pad10)") (class "Default")
      (node (ref "U3") (pin "10") (pinfunction "PA0-WKUP_10") (pintype "bidirectional+no_connect"))
    )
    (net (code "69") (name "unconnected-(U3A-PA3-Pad13)") (class "Default")
      (node (ref "U3") (pin "13") (pinfunction "PA3_13") (pintype "bidirectional+no_connect"))
    )
    (net (code "70") (name "unconnected-(U3A-PA4-Pad14)") (class "Default")
      (node (ref "U3") (pin "14") (pinfunction "PA4_14") (pintype "bidirectional+no_connect"))
    )
    (net (code "71") (name "unconnected-(U3A-PA5-Pad15)") (class "Default")
      (node (ref "U3") (pin "15") (pinfunction "PA5_15") (pintype "bidirectional+no_connect"))
    )
    (net (code "72") (name "unconnected-(U3A-PA6-Pad16)") (class "Default")
      (node (ref "U3") (pin "16") (pinfunction "PA6_16") (pintype "bidirectional+no_connect"))
    )
    (net (code "73") (name "unconnected-(U3A-PA7-Pad17)") (class "Default")
      (node (ref "U3") (pin "17") (pinfunction "PA7_17") (pintype "bidirectional+no_connect"))
    )
    (net (code "74") (name "unconnected-(U3A-PA8-Pad29)") (class "Default")
      (node (ref "U3") (pin "29") (pinfunction "PA8_29") (pintype "bidirectional+no_connect"))
    )
    (net (code "75") (name "unconnected-(U3A-PA13-Pad34)") (class "Default")
      (node (ref "U3") (pin "34") (pinfunction "PA13_34") (pintype "bidirectional+no_connect"))
    )
    (net (code "76") (name "unconnected-(U3A-PA14-Pad37)") (class "Default")
      (node (ref "U3") (pin "37") (pinfunction "PA14_37") (pintype "bidirectional+no_connect"))
    )
    (net (code "77") (name "unconnected-(U3A-PA15-Pad38)") (class "Default")
      (node (ref "U3") (pin "38") (pinfunction "PA15_38") (pintype "bidirectional+no_connect"))
    )
    (net (code "78") (name "unconnected-(U3A-PB3-Pad39)") (class "Default")
      (node (ref "U3") (pin "39") (pinfunction "PB3_39") (pintype "bidirectional+no_connect"))
    )
    (net (code "79") (name "unconnected-(U3A-PB4-Pad40)") (class "Default")
      (node (ref "U3") (pin "40") (pinfunction "PB4_40") (pintype "bidirectional+no_connect"))
    )
    (net (code "80") (name "unconnected-(U3A-PB11-Pad22)") (class "Default")
      (node (ref "U3") (pin "22") (pinfunction "PB11_22") (pintype "bidirectional+no_connect"))
    )
    (net (code "81") (name "unconnected-(U3A-PB14-Pad27)") (class "Default")
      (node (ref "U3") (pin "27") (pinfunction "PB14_27") (pintype "bidirectional+no_connect"))
    )
    (net (code "82") (name "unconnected-(U3A-PC13-TAMPER-RTC-Pad2)") (class "Default")
      (node (ref "U3") (pin "2") (pinfunction "PC13-TAMPER-RTC_2") (pintype "bidirectional+no_connect"))
    )
    (net (code "83") (name "unconnected-(USBC1-Pad0)") (class "Default")
      (node (ref "USBC1") (pin "0") (pinfunction "0_0") (pintype "passive+no_connect"))
    )
    (net (code "84") (name "unconnected-(USBC1-Pad0)_1") (class "Default")
      (node (ref "USBC1") (pin "0") (pinfunction "0_0") (pintype "passive+no_connect"))
    )
    (net (code "85") (name "unconnected-(USBC1-Pad0)_2") (class "Default")
      (node (ref "USBC1") (pin "0") (pinfunction "0_0") (pintype "passive+no_connect"))
    )
    (net (code "86") (name "unconnected-(USBC1-Pad0)_3") (class "Default")
      (node (ref "USBC1") (pin "0") (pinfunction "0_0") (pintype "passive+no_connect"))
    )
    (net (code "87") (name "unconnected-(X1-Pad2)") (class "Default")
      (node (ref "X1") (pin "2") (pinfunction "2_2") (pintype "passive+no_connect"))
    )
    (net (code "88") (name "unconnected-(X1-Pad3)") (class "Default")
      (node (ref "X1") (pin "3") (pinfunction "3_3") (pintype "passive+no_connect"))
    )
  )
)
